# Power-Monitor.net
KiCad netlist of a schematic drawn in Altium Designer
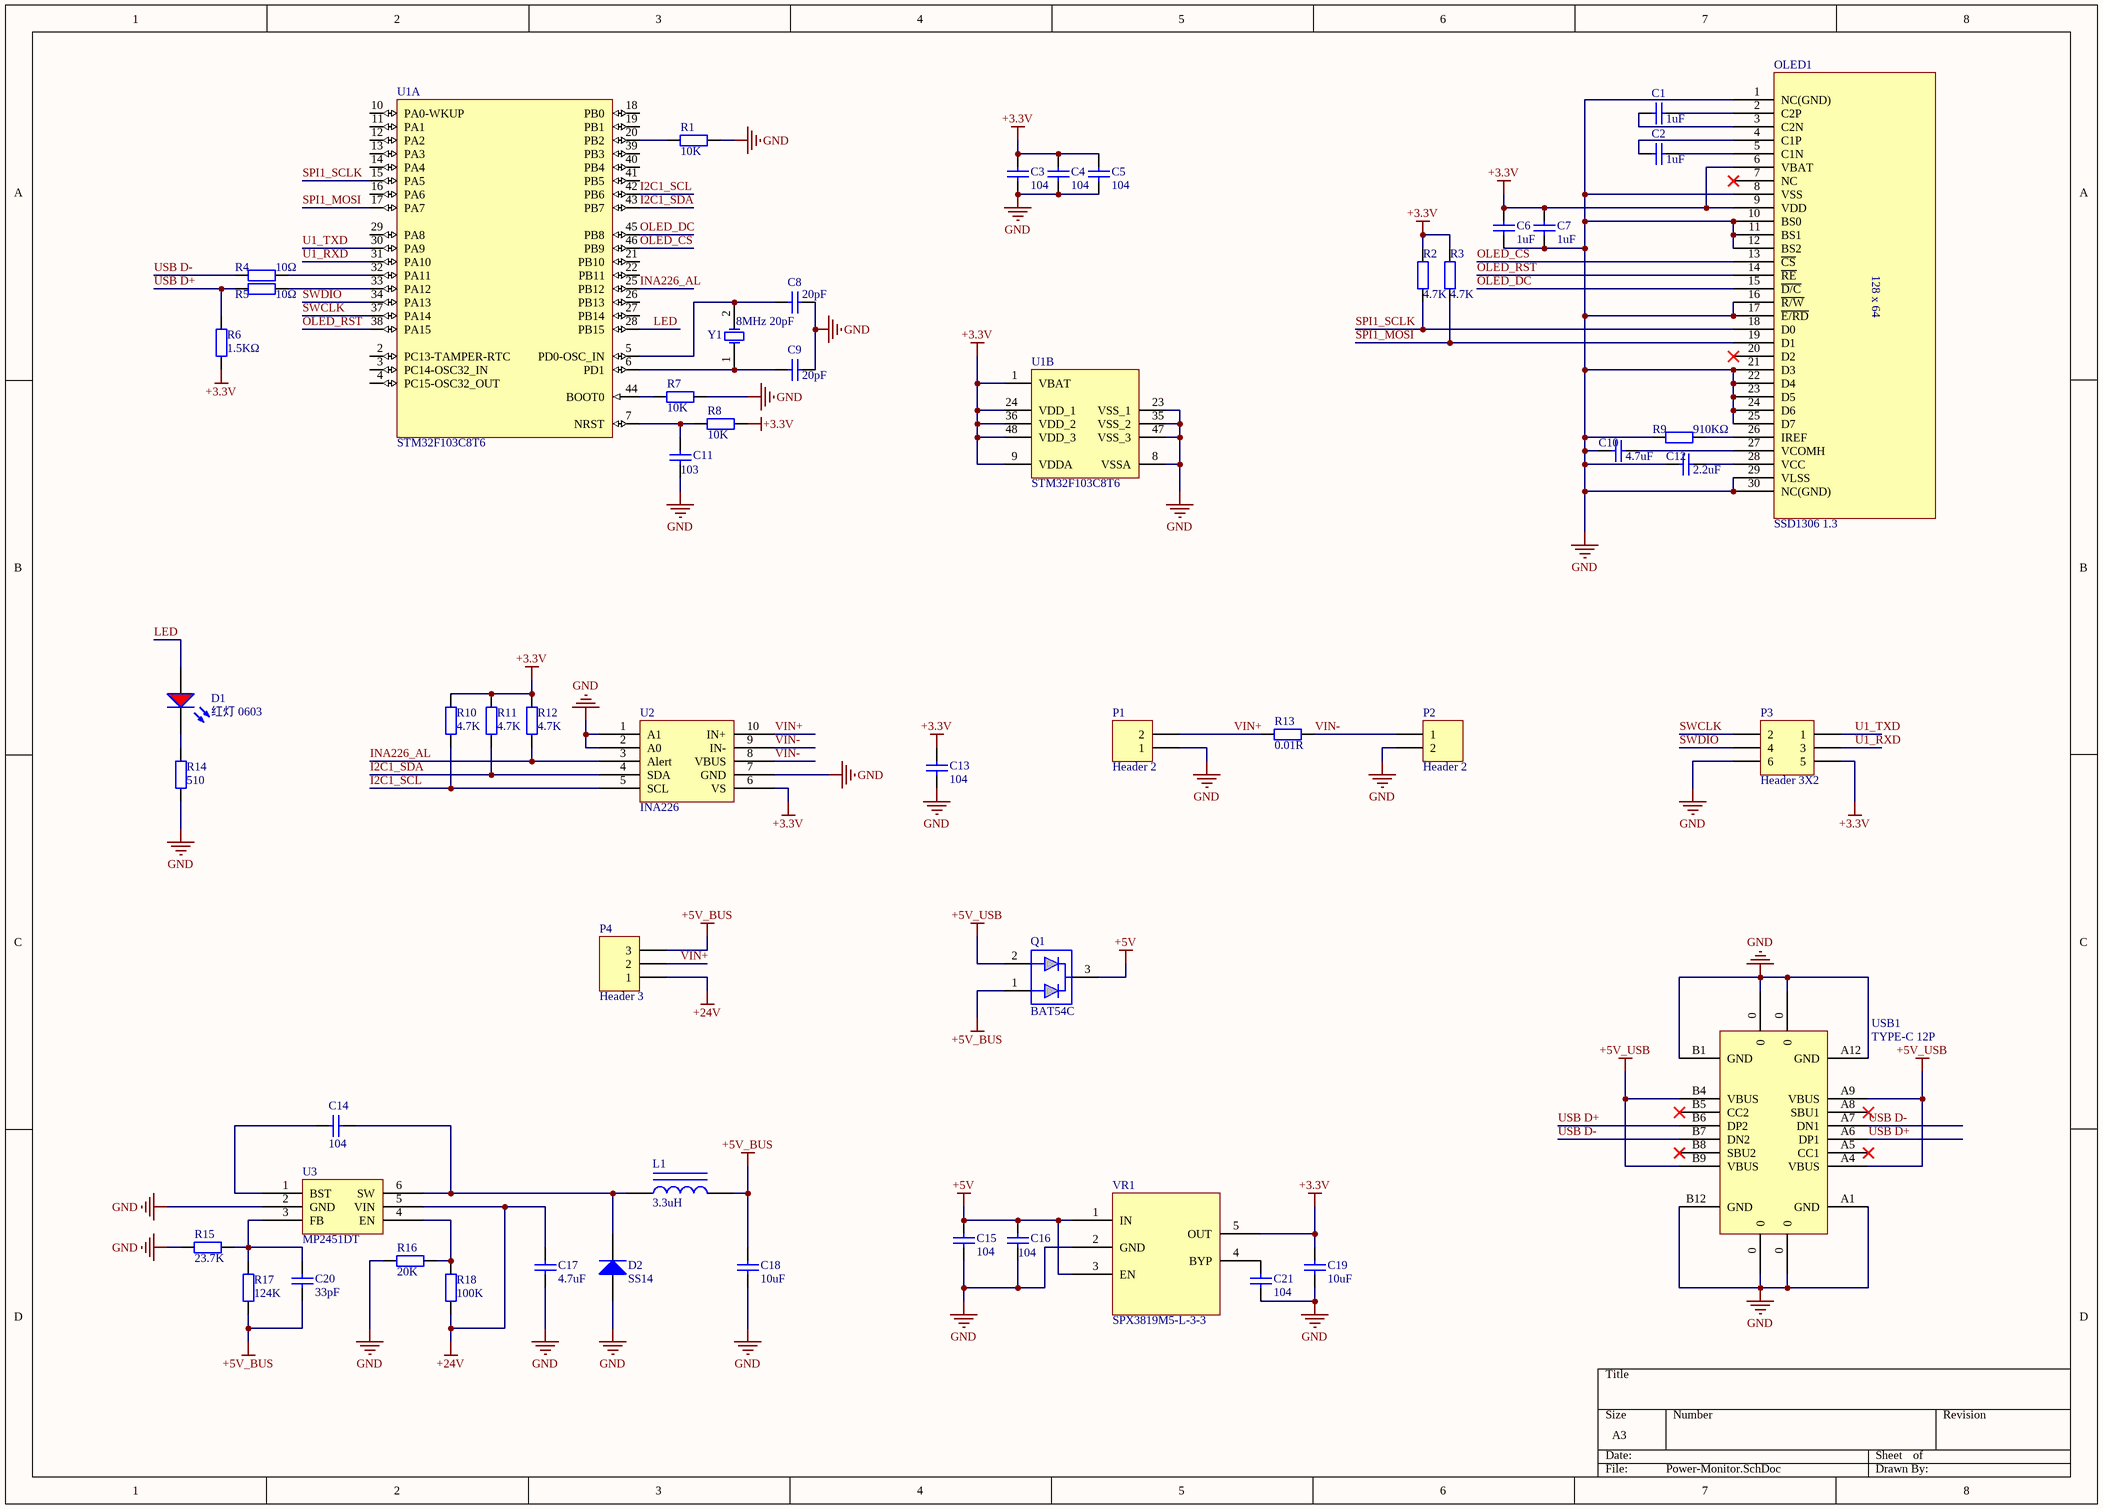
[diagram p0: Power-Monitor.SchDoc]

(export (version "E")
  (design (tool "Eeschema 10.0.6"))
  (components
    (comp (ref "C1")
      (value "1uF")
      (footprint "0603_C")
      (description "贴片电容")
      (libsource (lib "Miscellaneous Devices LC") (part "0603 2.7pF (2R7) 0.25pF 50V"))
    )
    (comp (ref "C2")
      (value "1uF")
      (footprint "0603_C")
      (description "贴片电容")
      (libsource (lib "Miscellaneous Devices LC") (part "0603 2.7pF (2R7) 0.25pF 50V"))
    )
    (comp (ref "C3")
      (value "104")
      (footprint "0603_C")
      (description "贴片电容")
      (libsource (lib "Miscellaneous Devices LC") (part "0603 2.7pF (2R7) 0.25pF 50V"))
    )
    (comp (ref "C4")
      (value "104")
      (footprint "0603_C")
      (description "贴片电容")
      (libsource (lib "Miscellaneous Devices LC") (part "0603 2.7pF (2R7) 0.25pF 50V"))
    )
    (comp (ref "C5")
      (value "104")
      (footprint "0603_C")
      (description "贴片电容")
      (libsource (lib "Miscellaneous Devices LC") (part "0603 2.7pF (2R7) 0.25pF 50V"))
    )
    (comp (ref "C6")
      (value "1uF")
      (footprint "0603_C")
      (description "贴片电容")
      (libsource (lib "Miscellaneous Devices LC") (part "0603 2.7pF (2R7) 0.25pF 50V"))
    )
    (comp (ref "C7")
      (value "1uF")
      (footprint "0603_C")
      (description "贴片电容")
      (libsource (lib "Miscellaneous Devices LC") (part "0603 2.7pF (2R7) 0.25pF 50V"))
    )
    (comp (ref "C8")
      (value "20pF")
      (footprint "0603_C")
      (description "贴片电容")
      (libsource (lib "Miscellaneous Devices LC") (part "0603 2.7pF (2R7) 0.25pF 50V"))
    )
    (comp (ref "C9")
      (value "20pF")
      (footprint "0603_C")
      (description "贴片电容")
      (libsource (lib "Miscellaneous Devices LC") (part "0603 2.7pF (2R7) 0.25pF 50V"))
    )
    (comp (ref "C10")
      (value "4.7uF")
      (footprint "0603_C")
      (description "贴片电容")
      (libsource (lib "Miscellaneous Devices LC") (part "0603 2.7pF (2R7) 0.25pF 50V"))
    )
    (comp (ref "C11")
      (value "103")
      (footprint "0603_C")
      (description "Capacitor")
      (fields (field (name "PUBLISHER") "Altium Limited"))
      (libsource (lib "Miscellaneous Devices") (part "Cap"))
    )
    (comp (ref "C12")
      (value "2.2uF")
      (footprint "0603_C")
      (description "贴片电容")
      (libsource (lib "Miscellaneous Devices LC") (part "0603 2.7pF (2R7) 0.25pF 50V"))
    )
    (comp (ref "C13")
      (value "104")
      (footprint "0603_C")
      (description "贴片电容")
      (libsource (lib "Miscellaneous Devices LC") (part "0603 2.7pF (2R7) 0.25pF 50V"))
    )
    (comp (ref "C14")
      (value "104")
      (footprint "0603_C")
      (description "贴片电容")
      (libsource (lib "") (part "0603 2.7pF (2R7) 0.25pF 50V_1"))
    )
    (comp (ref "C15")
      (value "104")
      (footprint "0603_C")
      (description "贴片电容")
      (libsource (lib "Miscellaneous Devices LC") (part "0603 2.7pF (2R7) 0.25pF 50V"))
    )
    (comp (ref "C16")
      (value "104")
      (footprint "0603_C")
      (description "贴片电容")
      (libsource (lib "Miscellaneous Devices LC") (part "0603 2.7pF (2R7) 0.25pF 50V"))
    )
    (comp (ref "C17")
      (value "4.7uF")
      (footprint "1206_C")
      (description "贴片电容")
      (libsource (lib "") (part "0603 2.7pF (2R7) 0.25pF 50V_1"))
    )
    (comp (ref "C18")
      (value "10uF")
      (footprint "0603_C")
      (description "贴片电容")
      (libsource (lib "") (part "0603 2.7pF (2R7) 0.25pF 50V_1"))
    )
    (comp (ref "C19")
      (value "10uF")
      (footprint "0603_C")
      (description "贴片电容")
      (libsource (lib "") (part "0603 2.7pF (2R7) 0.25pF 50V_1"))
    )
    (comp (ref "C20")
      (value "33pF")
      (footprint "0603_C")
      (description "贴片电容")
      (libsource (lib "") (part "0603 2.7pF (2R7) 0.25pF 50V_1"))
    )
    (comp (ref "C21")
      (value "104")
      (footprint "0603_C")
      (description "贴片电容")
      (libsource (lib "") (part "0603 2.7pF (2R7) 0.25pF 50V_1"))
    )
    (comp (ref "D1")
      (value "红灯 0603")
      (footprint "0603_LED_S1")
      (description "发光二极管")
      (libsource (lib "Miscellaneous Devices LC") (part "0805 红灯"))
    )
    (comp (ref "D2")
      (value "SS14")
      (footprint "SMA(DO-214AC)_S1")
      (description "二极管")
      (libsource (lib "Diode") (part "SMA(DO-214AC) SS54"))
    )
    (comp (ref "L1")
      (value "3.3uH")
      (footprint "SMD,4.6x4.1x2.0mm")
      (description "贴片电感")
      (libsource (lib "My_Schlib") (part "电感"))
    )
    (comp (ref "OLED1")
      (value "SSD1306 1.3")
      (footprint "SSD1306 1.3'")
      (libsource (lib "Schlib1") (part "SSD1306 1.3"))
    )
    (comp (ref "P1")
      (value "Header 2")
      (footprint "CDS-508H-2P")
      (description "Header, 2-Pin")
      (fields (field (name "PUBLISHER") "Altium Limited"))
      (libsource (lib "") (part "Header 2_1"))
    )
    (comp (ref "P2")
      (value "Header 2")
      (footprint "CDS-508H-2P")
      (description "Header, 2-Pin")
      (fields (field (name "PUBLISHER") "Altium Limited"))
      (libsource (lib "Miscellaneous Connectors") (part "Header 2"))
    )
    (comp (ref "P3")
      (value "Header 3X2")
      (footprint "201S2X3")
      (description "Header, 3-Pin, Dual row")
      (fields (field (name "PUBLISHER") "Altium Limited"))
      (libsource (lib "Miscellaneous Connectors") (part "Header 3X2"))
    )
    (comp (ref "P4")
      (value "Header 3")
      (footprint "HDR1X3")
      (description "Header, 3-Pin")
      (fields (field (name "PUBLISHER") "Altium Limited"))
      (libsource (lib "Miscellaneous Connectors") (part "Header 3"))
    )
    (comp (ref "Q1")
      (value "BAT54C")
      (footprint "SOT-23(SOT-23-3)")
      (description "BAT54C/KL3")
      (libsource (lib "YS_STM32F407_MC") (part "BAT54C"))
    )
    (comp (ref "R1")
      (value "10K")
      (footprint "0603_R")
      (description "Resistor")
      (fields (field (name "PUBLISHER") "Altium Limited"))
      (libsource (lib "Miscellaneous Devices") (part "Res2"))
    )
    (comp (ref "R2")
      (value "4.7K")
      (footprint "0603_R")
      (description "Resistor")
      (fields (field (name "PUBLISHER") "Altium Limited"))
      (libsource (lib "") (part "Res2_1"))
    )
    (comp (ref "R3")
      (value "4.7K")
      (footprint "0603_R")
      (description "Resistor")
      (fields (field (name "PUBLISHER") "Altium Limited"))
      (libsource (lib "") (part "Res2_1"))
    )
    (comp (ref "R4")
      (value "10Ω")
      (footprint "0603_R")
      (description "贴片电阻")
      (libsource (lib "") (part "0603 330Ω (3300) 1%_1"))
    )
    (comp (ref "R5")
      (value "10Ω")
      (footprint "0603_R")
      (description "贴片电阻")
      (libsource (lib "") (part "0603 330Ω (3300) 1%_1"))
    )
    (comp (ref "R6")
      (value "1.5KΩ")
      (footprint "0603_R")
      (description "贴片电阻")
      (libsource (lib "Miscellaneous Devices LC") (part "0603 330Ω (3300) 1%"))
    )
    (comp (ref "R7")
      (value "10K")
      (footprint "0603_R")
      (description "Resistor")
      (fields (field (name "PUBLISHER") "Altium Limited"))
      (libsource (lib "Miscellaneous Devices") (part "Res2"))
    )
    (comp (ref "R8")
      (value "10K")
      (footprint "0603_R")
      (description "Resistor")
      (fields (field (name "PUBLISHER") "Altium Limited"))
      (libsource (lib "Miscellaneous Devices") (part "Res2"))
    )
    (comp (ref "R9")
      (value "910KΩ")
      (footprint "0603_R")
      (description "贴片电阻")
      (libsource (lib "") (part "0603 330Ω (3300) 1%_1"))
    )
    (comp (ref "R10")
      (value "4.7K")
      (footprint "0603_R")
      (description "Resistor")
      (fields (field (name "PUBLISHER") "Altium Limited"))
      (libsource (lib "") (part "Res2_1"))
    )
    (comp (ref "R11")
      (value "4.7K")
      (footprint "0603_R")
      (description "Resistor")
      (fields (field (name "PUBLISHER") "Altium Limited"))
      (libsource (lib "") (part "Res2_1"))
    )
    (comp (ref "R12")
      (value "4.7K")
      (footprint "0603_R")
      (description "Resistor")
      (fields (field (name "PUBLISHER") "Altium Limited"))
      (libsource (lib "") (part "Res2_1"))
    )
    (comp (ref "R13")
      (value "0.01R")
      (footprint "2512_R")
      (description "Resistor")
      (fields (field (name "PUBLISHER") "Altium Limited"))
      (libsource (lib "Miscellaneous Devices") (part "Res2"))
    )
    (comp (ref "R14")
      (value "510")
      (footprint "0603_R")
      (description "贴片电阻")
      (libsource (lib "Miscellaneous Devices LC") (part "0603 330Ω (3300) 1%"))
    )
    (comp (ref "R15")
      (value "23.7K")
      (footprint "0603_R")
      (description "Resistor")
      (fields (field (name "PUBLISHER") "Altium Limited"))
      (libsource (lib "") (part "Res2_2"))
    )
    (comp (ref "R16")
      (value "20K")
      (footprint "0603_R")
      (description "Resistor")
      (fields (field (name "PUBLISHER") "Altium Limited"))
      (libsource (lib "") (part "Res2_2"))
    )
    (comp (ref "R17")
      (value "124K")
      (footprint "0603_R")
      (description "Resistor")
      (fields (field (name "PUBLISHER") "Altium Limited"))
      (libsource (lib "") (part "Res2_1"))
    )
    (comp (ref "R18")
      (value "100K")
      (footprint "0603_R")
      (description "Resistor")
      (fields (field (name "PUBLISHER") "Altium Limited"))
      (libsource (lib "") (part "Res2_1"))
    )
    (comp (ref "U1")
      (value "STM32F103C8T6")
      (footprint "LQFP-48_7x7x05P")
      (description "ARM")
      (libsource (lib "Miscellaneous Devices LC") (part "STM32F103C8T6"))
    )
    (comp (ref "U2") (value "INA226") (footprint "VSSOP-10") (libsource (lib "My_Schlib") (part "INA226")))
    (comp (ref "U3")
      (value "MP2451DT")
      (footprint "SOT-23-6")
      (description "DCDC  36V 0.6A")
      (libsource (lib "My_Schlib") (part "MP2451DT"))
    )
    (comp (ref "USB1")
      (value "TYPE-C 12P")
      (footprint "TYPE-C 12P 贴片")
      (libsource (lib "Schlib1") (part "TYPE-C 12P"))
    )
    (comp (ref "VR1")
      (value "SPX3819M5-L-3-3")
      (footprint "SOT-23-5")
      (libsource (lib "Schlib1") (part "SPX3819M5-L-3-3"))
    )
    (comp (ref "Y1")
      (value "8MHz 20pF")
      (footprint "SMD-5032_2P")
      (description "贴片晶振")
      (libsource (lib "Miscellaneous Devices LC") (part "SMD-5032_2P 8MHz 20ppm 20pF"))
    )
  )
  (nets
    (net (code "1") (name "+3.3V") (class "Default")
      (node (ref "C13") (pin "2") (pinfunction "2_2") (pintype "passive"))
      (node (ref "C19") (pin "1") (pinfunction "1_1") (pintype "passive"))
      (node (ref "C3") (pin "2") (pinfunction "2_2") (pintype "passive"))
      (node (ref "C4") (pin "2") (pinfunction "2_2") (pintype "passive"))
      (node (ref "C5") (pin "2") (pinfunction "2_2") (pintype "passive"))
      (node (ref "C6") (pin "2") (pinfunction "2_2") (pintype "passive"))
      (node (ref "C7") (pin "2") (pinfunction "2_2") (pintype "passive"))
      (node (ref "OLED1") (pin "6") (pinfunction "VBAT_6") (pintype "passive"))
      (node (ref "OLED1") (pin "9") (pinfunction "VDD_9") (pintype "passive"))
      (node (ref "P3") (pin "5") (pinfunction "5_5") (pintype "passive"))
      (node (ref "R10") (pin "1") (pinfunction "1_1") (pintype "passive"))
      (node (ref "R11") (pin "1") (pinfunction "1_1") (pintype "passive"))
      (node (ref "R12") (pin "1") (pinfunction "1_1") (pintype "passive"))
      (node (ref "R2") (pin "1") (pinfunction "1_1") (pintype "passive"))
      (node (ref "R3") (pin "1") (pinfunction "1_1") (pintype "passive"))
      (node (ref "R6") (pin "1") (pinfunction "1_1") (pintype "passive"))
      (node (ref "R8") (pin "1") (pinfunction "1_1") (pintype "passive"))
      (node (ref "U1") (pin "1") (pinfunction "VBAT_1") (pintype "power_in"))
      (node (ref "U1") (pin "24") (pinfunction "VDD_1_24") (pintype "power_in"))
      (node (ref "U1") (pin "36") (pinfunction "VDD_2_36") (pintype "power_in"))
      (node (ref "U1") (pin "48") (pinfunction "VDD_3_48") (pintype "power_in"))
      (node (ref "U1") (pin "9") (pinfunction "VDDA_9") (pintype "power_in"))
      (node (ref "U2") (pin "6") (pinfunction "VS_6") (pintype "passive"))
      (node (ref "VR1") (pin "5") (pinfunction "OUT_5") (pintype "passive"))
    )
    (net (code "2") (name "+5V") (class "Default")
      (node (ref "C15") (pin "2") (pinfunction "2_2") (pintype "passive"))
      (node (ref "C16") (pin "2") (pinfunction "2_2") (pintype "passive"))
      (node (ref "Q1") (pin "3") (pinfunction "COM_CATHODE_3") (pintype "passive"))
      (node (ref "VR1") (pin "1") (pinfunction "IN_1") (pintype "passive"))
      (node (ref "VR1") (pin "3") (pinfunction "EN_3") (pintype "passive"))
    )
    (net (code "3") (name "+5V_BUS") (class "Default")
      (node (ref "C18") (pin "2") (pinfunction "2_2") (pintype "passive"))
      (node (ref "C20") (pin "1") (pinfunction "1_1") (pintype "passive"))
      (node (ref "L1") (pin "2") (pinfunction "2_2") (pintype "passive"))
      (node (ref "P4") (pin "3") (pinfunction "3_3") (pintype "passive"))
      (node (ref "Q1") (pin "1") (pinfunction "DIODE1_1") (pintype "passive"))
      (node (ref "R17") (pin "2") (pinfunction "2_2") (pintype "passive"))
    )
    (net (code "4") (name "+5V_USB") (class "Default")
      (node (ref "Q1") (pin "2") (pinfunction "DIODE2_2") (pintype "passive"))
      (node (ref "USB1") (pin "A4") (pinfunction "VBUS_A4") (pintype "passive"))
      (node (ref "USB1") (pin "A9") (pinfunction "VBUS_A9") (pintype "passive"))
      (node (ref "USB1") (pin "B4") (pinfunction "VBUS_B4") (pintype "passive"))
      (node (ref "USB1") (pin "B9") (pinfunction "VBUS_B9") (pintype "passive"))
    )
    (net (code "5") (name "+24V") (class "Default")
      (node (ref "C17") (pin "2") (pinfunction "2_2") (pintype "passive"))
      (node (ref "P4") (pin "1") (pinfunction "1_1") (pintype "passive"))
      (node (ref "R18") (pin "2") (pinfunction "2_2") (pintype "passive"))
      (node (ref "U3") (pin "5") (pinfunction "VIN_5") (pintype "passive"))
    )
    (net (code "6") (name "/I2C1_SCL") (class "Default")
      (node (ref "R10") (pin "2") (pinfunction "2_2") (pintype "passive"))
      (node (ref "U1") (pin "42") (pinfunction "PB6_42") (pintype "bidirectional"))
      (node (ref "U2") (pin "5") (pinfunction "SCL_5") (pintype "passive"))
    )
    (net (code "7") (name "/I2C1_SDA") (class "Default")
      (node (ref "R11") (pin "2") (pinfunction "2_2") (pintype "passive"))
      (node (ref "U1") (pin "43") (pinfunction "PB7_43") (pintype "bidirectional"))
      (node (ref "U2") (pin "4") (pinfunction "SDA_4") (pintype "passive"))
    )
    (net (code "8") (name "/INA226_AL") (class "Default")
      (node (ref "R12") (pin "2") (pinfunction "2_2") (pintype "passive"))
      (node (ref "U1") (pin "25") (pinfunction "PB12_25") (pintype "bidirectional"))
      (node (ref "U2") (pin "3") (pinfunction "Alert_3") (pintype "passive"))
    )
    (net (code "9") (name "/LED") (class "Default")
      (node (ref "D1") (pin "A") (pinfunction "A_A") (pintype "passive"))
      (node (ref "U1") (pin "28") (pinfunction "PB15_28") (pintype "bidirectional"))
    )
    (net (code "10") (name "/OLED_CS") (class "Default")
      (node (ref "OLED1") (pin "13") (pinfunction "~{CS}_13") (pintype "passive"))
      (node (ref "U1") (pin "46") (pinfunction "PB9_46") (pintype "bidirectional"))
    )
    (net (code "11") (name "/OLED_DC") (class "Default")
      (node (ref "OLED1") (pin "15") (pinfunction "~{D/C}_15") (pintype "passive"))
      (node (ref "U1") (pin "45") (pinfunction "PB8_45") (pintype "bidirectional"))
    )
    (net (code "12") (name "/OLED_RST") (class "Default")
      (node (ref "OLED1") (pin "14") (pinfunction "~{RE}_14") (pintype "passive"))
      (node (ref "U1") (pin "38") (pinfunction "PA15_38") (pintype "bidirectional"))
    )
    (net (code "13") (name "/SPI1_MOSI") (class "Default")
      (node (ref "OLED1") (pin "19") (pinfunction "D1_19") (pintype "passive"))
      (node (ref "R3") (pin "2") (pinfunction "2_2") (pintype "passive"))
      (node (ref "U1") (pin "17") (pinfunction "PA7_17") (pintype "bidirectional"))
    )
    (net (code "14") (name "/SPI1_SCLK") (class "Default")
      (node (ref "OLED1") (pin "18") (pinfunction "D0_18") (pintype "passive"))
      (node (ref "R2") (pin "2") (pinfunction "2_2") (pintype "passive"))
      (node (ref "U1") (pin "15") (pinfunction "PA5_15") (pintype "bidirectional"))
    )
    (net (code "15") (name "/SWCLK") (class "Default")
      (node (ref "P3") (pin "2") (pinfunction "2_2") (pintype "passive"))
      (node (ref "U1") (pin "37") (pinfunction "PA14_37") (pintype "bidirectional"))
    )
    (net (code "16") (name "/SWDIO") (class "Default")
      (node (ref "P3") (pin "4") (pinfunction "4_4") (pintype "passive"))
      (node (ref "U1") (pin "34") (pinfunction "PA13_34") (pintype "bidirectional"))
    )
    (net (code "17") (name "/U1_RXD") (class "Default")
      (node (ref "P3") (pin "3") (pinfunction "3_3") (pintype "passive"))
      (node (ref "U1") (pin "31") (pinfunction "PA10_31") (pintype "bidirectional"))
    )
    (net (code "18") (name "/U1_TXD") (class "Default")
      (node (ref "P3") (pin "1") (pinfunction "1_1") (pintype "passive"))
      (node (ref "U1") (pin "30") (pinfunction "PA9_30") (pintype "bidirectional"))
    )
    (net (code "19") (name "/USB D+") (class "Default")
      (node (ref "R5") (pin "1") (pinfunction "1_1") (pintype "passive"))
      (node (ref "R6") (pin "2") (pinfunction "2_2") (pintype "passive"))
      (node (ref "USB1") (pin "A6") (pinfunction "DP1_A6") (pintype "passive"))
      (node (ref "USB1") (pin "B6") (pinfunction "DP2_B6") (pintype "passive"))
    )
    (net (code "20") (name "/USB D-") (class "Default")
      (node (ref "R4") (pin "1") (pinfunction "1_1") (pintype "passive"))
      (node (ref "USB1") (pin "A7") (pinfunction "DN1_A7") (pintype "passive"))
      (node (ref "USB1") (pin "B7") (pinfunction "DN2_B7") (pintype "passive"))
    )
    (net (code "21") (name "/VIN+") (class "Default")
      (node (ref "P1") (pin "2") (pinfunction "2_2") (pintype "passive"))
      (node (ref "P4") (pin "2") (pinfunction "2_2") (pintype "passive"))
      (node (ref "R13") (pin "2") (pinfunction "2_2") (pintype "passive"))
      (node (ref "U2") (pin "10") (pinfunction "IN+_10") (pintype "passive"))
    )
    (net (code "22") (name "/VIN-") (class "Default")
      (node (ref "P2") (pin "1") (pinfunction "1_1") (pintype "passive"))
      (node (ref "R13") (pin "1") (pinfunction "1_1") (pintype "passive"))
      (node (ref "U2") (pin "8") (pinfunction "VBUS_8") (pintype "passive"))
      (node (ref "U2") (pin "9") (pinfunction "IN-_9") (pintype "passive"))
    )
    (net (code "23") (name "GND") (class "Default")
      (node (ref "C10") (pin "2") (pinfunction "2_2") (pintype "passive"))
      (node (ref "C11") (pin "2") (pinfunction "2_2") (pintype "passive"))
      (node (ref "C12") (pin "2") (pinfunction "2_2") (pintype "passive"))
      (node (ref "C13") (pin "1") (pinfunction "1_1") (pintype "passive"))
      (node (ref "C15") (pin "1") (pinfunction "1_1") (pintype "passive"))
      (node (ref "C16") (pin "1") (pinfunction "1_1") (pintype "passive"))
      (node (ref "C17") (pin "1") (pinfunction "1_1") (pintype "passive"))
      (node (ref "C18") (pin "1") (pinfunction "1_1") (pintype "passive"))
      (node (ref "C19") (pin "2") (pinfunction "2_2") (pintype "passive"))
      (node (ref "C21") (pin "2") (pinfunction "2_2") (pintype "passive"))
      (node (ref "C3") (pin "1") (pinfunction "1_1") (pintype "passive"))
      (node (ref "C4") (pin "1") (pinfunction "1_1") (pintype "passive"))
      (node (ref "C5") (pin "1") (pinfunction "1_1") (pintype "passive"))
      (node (ref "C6") (pin "1") (pinfunction "1_1") (pintype "passive"))
      (node (ref "C7") (pin "1") (pinfunction "1_1") (pintype "passive"))
      (node (ref "C8") (pin "2") (pinfunction "2_2") (pintype "passive"))
      (node (ref "C9") (pin "2") (pinfunction "2_2") (pintype "passive"))
      (node (ref "D2") (pin "1") (pinfunction "A_1") (pintype "passive"))
      (node (ref "OLED1") (pin "1") (pinfunction "NC(GND)_1") (pintype "passive"))
      (node (ref "OLED1") (pin "10") (pinfunction "BS0_10") (pintype "passive"))
      (node (ref "OLED1") (pin "11") (pinfunction "BS1_11") (pintype "passive"))
      (node (ref "OLED1") (pin "12") (pinfunction "BS2_12") (pintype "passive"))
      (node (ref "OLED1") (pin "16") (pinfunction "~{R/W}_16") (pintype "passive"))
      (node (ref "OLED1") (pin "17") (pinfunction "~{E/RD}_17") (pintype "passive"))
      (node (ref "OLED1") (pin "21") (pinfunction "D3_21") (pintype "passive"))
      (node (ref "OLED1") (pin "22") (pinfunction "D4_22") (pintype "passive"))
      (node (ref "OLED1") (pin "23") (pinfunction "D5_23") (pintype "passive"))
      (node (ref "OLED1") (pin "24") (pinfunction "D6_24") (pintype "passive"))
      (node (ref "OLED1") (pin "25") (pinfunction "D7_25") (pintype "passive"))
      (node (ref "OLED1") (pin "29") (pinfunction "VLSS_29") (pintype "passive"))
      (node (ref "OLED1") (pin "30") (pinfunction "NC(GND)_30") (pintype "passive"))
      (node (ref "OLED1") (pin "8") (pinfunction "VSS_8") (pintype "passive"))
      (node (ref "P1") (pin "1") (pinfunction "1_1") (pintype "passive"))
      (node (ref "P2") (pin "2") (pinfunction "2_2") (pintype "passive"))
      (node (ref "P3") (pin "6") (pinfunction "6_6") (pintype "passive"))
      (node (ref "R1") (pin "1") (pinfunction "1_1") (pintype "passive"))
      (node (ref "R14") (pin "1") (pinfunction "1_1") (pintype "passive"))
      (node (ref "R15") (pin "1") (pinfunction "1_1") (pintype "passive"))
      (node (ref "R16") (pin "1") (pinfunction "1_1") (pintype "passive"))
      (node (ref "R7") (pin "1") (pinfunction "1_1") (pintype "passive"))
      (node (ref "R9") (pin "1") (pinfunction "1_1") (pintype "passive"))
      (node (ref "U1") (pin "23") (pinfunction "VSS_1_23") (pintype "power_in"))
      (node (ref "U1") (pin "35") (pinfunction "VSS_2_35") (pintype "power_in"))
      (node (ref "U1") (pin "47") (pinfunction "VSS_3_47") (pintype "power_in"))
      (node (ref "U1") (pin "8") (pinfunction "VSSA_8") (pintype "power_in"))
      (node (ref "U2") (pin "1") (pinfunction "A1_1") (pintype "passive"))
      (node (ref "U2") (pin "2") (pinfunction "A0_2") (pintype "passive"))
      (node (ref "U2") (pin "7") (pinfunction "GND_7") (pintype "passive"))
      (node (ref "U3") (pin "2") (pinfunction "GND_2") (pintype "passive"))
      (node (ref "USB1") (pin "0") (pinfunction "0_0") (pintype "passive"))
      (node (ref "USB1") (pin "A1") (pinfunction "GND_A1") (pintype "passive"))
      (node (ref "USB1") (pin "A12") (pinfunction "GND_A12") (pintype "passive"))
      (node (ref "USB1") (pin "B1") (pinfunction "GND_B1") (pintype "passive"))
      (node (ref "USB1") (pin "B12") (pinfunction "GND_B12") (pintype "passive"))
      (node (ref "VR1") (pin "2") (pinfunction "GND_2") (pintype "passive"))
    )
    (net (code "24") (name "Net-(D1-PadK)") (class "Default")
      (node (ref "D1") (pin "K") (pinfunction "K_K") (pintype "passive"))
      (node (ref "R14") (pin "2") (pinfunction "2_2") (pintype "passive"))
    )
    (net (code "25") (name "Net-(D2-K)") (class "Default")
      (node (ref "C14") (pin "2") (pinfunction "2_2") (pintype "passive"))
      (node (ref "D2") (pin "2") (pinfunction "K_2") (pintype "passive"))
      (node (ref "L1") (pin "1") (pinfunction "1_1") (pintype "passive"))
      (node (ref "U3") (pin "6") (pinfunction "SW_6") (pintype "passive"))
    )
    (net (code "26") (name "Net-(OLED1-C1N)") (class "Default")
      (node (ref "C2") (pin "2") (pinfunction "2_2") (pintype "passive"))
      (node (ref "OLED1") (pin "5") (pinfunction "C1N_5") (pintype "passive"))
    )
    (net (code "27") (name "Net-(OLED1-C1P)") (class "Default")
      (node (ref "C2") (pin "1") (pinfunction "1_1") (pintype "passive"))
      (node (ref "OLED1") (pin "4") (pinfunction "C1P_4") (pintype "passive"))
    )
    (net (code "28") (name "Net-(OLED1-C2N)") (class "Default")
      (node (ref "C1") (pin "1") (pinfunction "1_1") (pintype "passive"))
      (node (ref "OLED1") (pin "3") (pinfunction "C2N_3") (pintype "passive"))
    )
    (net (code "29") (name "Net-(OLED1-C2P)") (class "Default")
      (node (ref "C1") (pin "2") (pinfunction "2_2") (pintype "passive"))
      (node (ref "OLED1") (pin "2") (pinfunction "C2P_2") (pintype "passive"))
    )
    (net (code "30") (name "Net-(OLED1-IREF)") (class "Default")
      (node (ref "OLED1") (pin "26") (pinfunction "IREF_26") (pintype "passive"))
      (node (ref "R9") (pin "2") (pinfunction "2_2") (pintype "passive"))
    )
    (net (code "31") (name "Net-(OLED1-VCC)") (class "Default")
      (node (ref "C12") (pin "1") (pinfunction "1_1") (pintype "passive"))
      (node (ref "OLED1") (pin "28") (pinfunction "VCC_28") (pintype "passive"))
    )
    (net (code "32") (name "Net-(OLED1-VCOMH)") (class "Default")
      (node (ref "C10") (pin "1") (pinfunction "1_1") (pintype "passive"))
      (node (ref "OLED1") (pin "27") (pinfunction "VCOMH_27") (pintype "passive"))
    )
    (net (code "33") (name "Net-(U1A-BOOT0)") (class "Default")
      (node (ref "R7") (pin "2") (pinfunction "2_2") (pintype "passive"))
      (node (ref "U1") (pin "44") (pinfunction "BOOT0_44") (pintype "input"))
    )
    (net (code "34") (name "Net-(U1A-NRST)") (class "Default")
      (node (ref "C11") (pin "1") (pinfunction "1_1") (pintype "passive"))
      (node (ref "R8") (pin "2") (pinfunction "2_2") (pintype "passive"))
      (node (ref "U1") (pin "7") (pinfunction "NRST_7") (pintype "bidirectional"))
    )
    (net (code "35") (name "Net-(U1A-PA11)") (class "Default")
      (node (ref "R4") (pin "2") (pinfunction "2_2") (pintype "passive"))
      (node (ref "U1") (pin "32") (pinfunction "PA11_32") (pintype "bidirectional"))
    )
    (net (code "36") (name "Net-(U1A-PA12)") (class "Default")
      (node (ref "R5") (pin "2") (pinfunction "2_2") (pintype "passive"))
      (node (ref "U1") (pin "33") (pinfunction "PA12_33") (pintype "bidirectional"))
    )
    (net (code "37") (name "Net-(U1A-PB2)") (class "Default")
      (node (ref "R1") (pin "2") (pinfunction "2_2") (pintype "passive"))
      (node (ref "U1") (pin "20") (pinfunction "PB2_20") (pintype "bidirectional"))
    )
    (net (code "38") (name "Net-(U1A-PD0-OSC_IN)") (class "Default")
      (node (ref "C8") (pin "1") (pinfunction "1_1") (pintype "passive"))
      (node (ref "U1") (pin "5") (pinfunction "PD0-OSC_IN_5") (pintype "bidirectional"))
      (node (ref "Y1") (pin "2") (pinfunction "OSC2_2") (pintype "passive"))
    )
    (net (code "39") (name "Net-(U1A-PD1)") (class "Default")
      (node (ref "C9") (pin "1") (pinfunction "1_1") (pintype "passive"))
      (node (ref "U1") (pin "6") (pinfunction "PD1_6") (pintype "bidirectional"))
      (node (ref "Y1") (pin "1") (pinfunction "OSC1_1") (pintype "passive"))
    )
    (net (code "40") (name "Net-(U3-BST)") (class "Default")
      (node (ref "C14") (pin "1") (pinfunction "1_1") (pintype "passive"))
      (node (ref "U3") (pin "1") (pinfunction "BST_1") (pintype "passive"))
    )
    (net (code "41") (name "Net-(U3-EN)") (class "Default")
      (node (ref "R16") (pin "2") (pinfunction "2_2") (pintype "passive"))
      (node (ref "R18") (pin "1") (pinfunction "1_1") (pintype "passive"))
      (node (ref "U3") (pin "4") (pinfunction "EN_4") (pintype "passive"))
    )
    (net (code "42") (name "Net-(U3-FB)") (class "Default")
      (node (ref "C20") (pin "2") (pinfunction "2_2") (pintype "passive"))
      (node (ref "R15") (pin "2") (pinfunction "2_2") (pintype "passive"))
      (node (ref "R17") (pin "1") (pinfunction "1_1") (pintype "passive"))
      (node (ref "U3") (pin "3") (pinfunction "FB_3") (pintype "passive"))
    )
    (net (code "43") (name "Net-(VR1-BYP)") (class "Default")
      (node (ref "C21") (pin "1") (pinfunction "1_1") (pintype "passive"))
      (node (ref "VR1") (pin "4") (pinfunction "BYP_4") (pintype "passive"))
    )
    (net (code "44") (name "unconnected-(OLED1-D2-Pad20)") (class "Default")
      (node (ref "OLED1") (pin "20") (pinfunction "D2_20") (pintype "passive+no_connect"))
    )
    (net (code "45") (name "unconnected-(OLED1-NC-Pad7)") (class "Default")
      (node (ref "OLED1") (pin "7") (pinfunction "NC_7") (pintype "passive+no_connect"))
    )
    (net (code "46") (name "unconnected-(U1A-PA0-WKUP-Pad10)") (class "Default")
      (node (ref "U1") (pin "10") (pinfunction "PA0-WKUP_10") (pintype "bidirectional"))
    )
    (net (code "47") (name "unconnected-(U1A-PA1-Pad11)") (class "Default")
      (node (ref "U1") (pin "11") (pinfunction "PA1_11") (pintype "bidirectional"))
    )
    (net (code "48") (name "unconnected-(U1A-PA2-Pad12)") (class "Default")
      (node (ref "U1") (pin "12") (pinfunction "PA2_12") (pintype "bidirectional"))
    )
    (net (code "49") (name "unconnected-(U1A-PA3-Pad13)") (class "Default")
      (node (ref "U1") (pin "13") (pinfunction "PA3_13") (pintype "bidirectional"))
    )
    (net (code "50") (name "unconnected-(U1A-PA4-Pad14)") (class "Default")
      (node (ref "U1") (pin "14") (pinfunction "PA4_14") (pintype "bidirectional"))
    )
    (net (code "51") (name "unconnected-(U1A-PA6-Pad16)") (class "Default")
      (node (ref "U1") (pin "16") (pinfunction "PA6_16") (pintype "bidirectional"))
    )
    (net (code "52") (name "unconnected-(U1A-PA8-Pad29)") (class "Default")
      (node (ref "U1") (pin "29") (pinfunction "PA8_29") (pintype "bidirectional"))
    )
    (net (code "53") (name "unconnected-(U1A-PB0-Pad18)") (class "Default")
      (node (ref "U1") (pin "18") (pinfunction "PB0_18") (pintype "bidirectional"))
    )
    (net (code "54") (name "unconnected-(U1A-PB1-Pad19)") (class "Default")
      (node (ref "U1") (pin "19") (pinfunction "PB1_19") (pintype "bidirectional"))
    )
    (net (code "55") (name "unconnected-(U1A-PB3-Pad39)") (class "Default")
      (node (ref "U1") (pin "39") (pinfunction "PB3_39") (pintype "bidirectional"))
    )
    (net (code "56") (name "unconnected-(U1A-PB4-Pad40)") (class "Default")
      (node (ref "U1") (pin "40") (pinfunction "PB4_40") (pintype "bidirectional"))
    )
    (net (code "57") (name "unconnected-(U1A-PB5-Pad41)") (class "Default")
      (node (ref "U1") (pin "41") (pinfunction "PB5_41") (pintype "bidirectional"))
    )
    (net (code "58") (name "unconnected-(U1A-PB10-Pad21)") (class "Default")
      (node (ref "U1") (pin "21") (pinfunction "PB10_21") (pintype "bidirectional"))
    )
    (net (code "59") (name "unconnected-(U1A-PB11-Pad22)") (class "Default")
      (node (ref "U1") (pin "22") (pinfunction "PB11_22") (pintype "bidirectional"))
    )
    (net (code "60") (name "unconnected-(U1A-PB13-Pad26)") (class "Default")
      (node (ref "U1") (pin "26") (pinfunction "PB13_26") (pintype "bidirectional"))
    )
    (net (code "61") (name "unconnected-(U1A-PB14-Pad27)") (class "Default")
      (node (ref "U1") (pin "27") (pinfunction "PB14_27") (pintype "bidirectional"))
    )
    (net (code "62") (name "unconnected-(U1A-PC13-TAMPER-RTC-Pad2)") (class "Default")
      (node (ref "U1") (pin "2") (pinfunction "PC13-TAMPER-RTC_2") (pintype "bidirectional"))
    )
    (net (code "63") (name "unconnected-(U1A-PC14-OSC32_IN-Pad3)") (class "Default")
      (node (ref "U1") (pin "3") (pinfunction "PC14-OSC32_IN_3") (pintype "bidirectional"))
    )
    (net (code "64") (name "unconnected-(U1A-PC15-OSC32_OUT-Pad4)") (class "Default")
      (node (ref "U1") (pin "4") (pinfunction "PC15-OSC32_OUT_4") (pintype "bidirectional"))
    )
    (net (code "65") (name "unconnected-(USB1-CC1-PadA5)") (class "Default")
      (node (ref "USB1") (pin "A5") (pinfunction "CC1_A5") (pintype "passive+no_connect"))
    )
    (net (code "66") (name "unconnected-(USB1-CC2-PadB5)") (class "Default")
      (node (ref "USB1") (pin "B5") (pinfunction "CC2_B5") (pintype "passive+no_connect"))
    )
    (net (code "67") (name "unconnected-(USB1-SBU1-PadA8)") (class "Default")
      (node (ref "USB1") (pin "A8") (pinfunction "SBU1_A8") (pintype "passive+no_connect"))
    )
    (net (code "68") (name "unconnected-(USB1-SBU2-PadB8)") (class "Default")
      (node (ref "USB1") (pin "B8") (pinfunction "SBU2_B8") (pintype "passive+no_connect"))
    )
  )
)
